# EnvironmentalSensor.net
KiCad netlist of a schematic drawn in Altium Designer
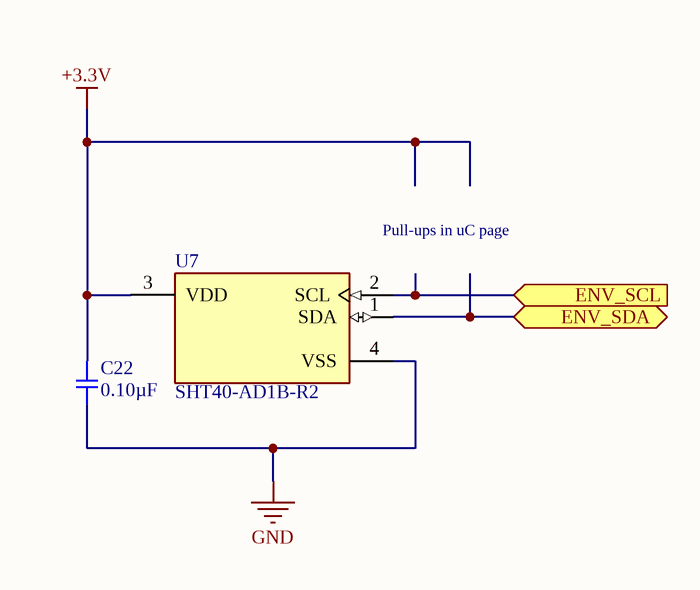
[diagram p0: EnvironmentalSensor.SchDoc]

(export (version "E")
  (design (tool "Eeschema 10.0.6"))
  (components
    (comp (ref "C22")
      (value "0.10µF")
      (footprint "SMD-0402C")
      (description "CAP CER 0.1UF 16V X7R 0402")
      (fields
        (field (name "DIGI-KEY PART NUMBER") "490-4759-1-ND")
        (field (name "PART NUMBER") "GCM155R71C104KA55D")
      )
      (libsource (lib "capacitor_murata_0402") (part "GCM155R71C104KA55D"))
    )
    (comp (ref "U7")
      (value "SHT40-AD1B-R2")
      (footprint "FP-SHT40-AD1B-R2-MFG")
      (description "SENSOR HUMIDITY 100 RH SMD")
      (libsource (lib "Altium Content Vault") (part "985d6b895d3abb4f56b1b691ea450a8"))
    )
  )
  (nets
    (net (code "1") (name "+3.3V") (class "Default")
      (node (ref "C22") (pin "1") (pinfunction "1_1") (pintype "passive"))
      (node (ref "U7") (pin "3") (pinfunction "VDD_3") (pintype "power_in"))
    )
    (net (code "2") (name "/ENV_SCL") (class "Default")
      (node (ref "U7") (pin "2") (pinfunction "SCL_2") (pintype "input"))
    )
    (net (code "3") (name "/ENV_SDA") (class "Default")
      (node (ref "U7") (pin "1") (pinfunction "SDA_1") (pintype "bidirectional"))
    )
    (net (code "4") (name "GND") (class "Default")
      (node (ref "C22") (pin "2") (pinfunction "2_2") (pintype "passive"))
      (node (ref "U7") (pin "4") (pinfunction "VSS_4") (pintype "power_in"))
    )
  )
)
